# trapezoid.net
KiCad netlist of a schematic drawn in EAGLE
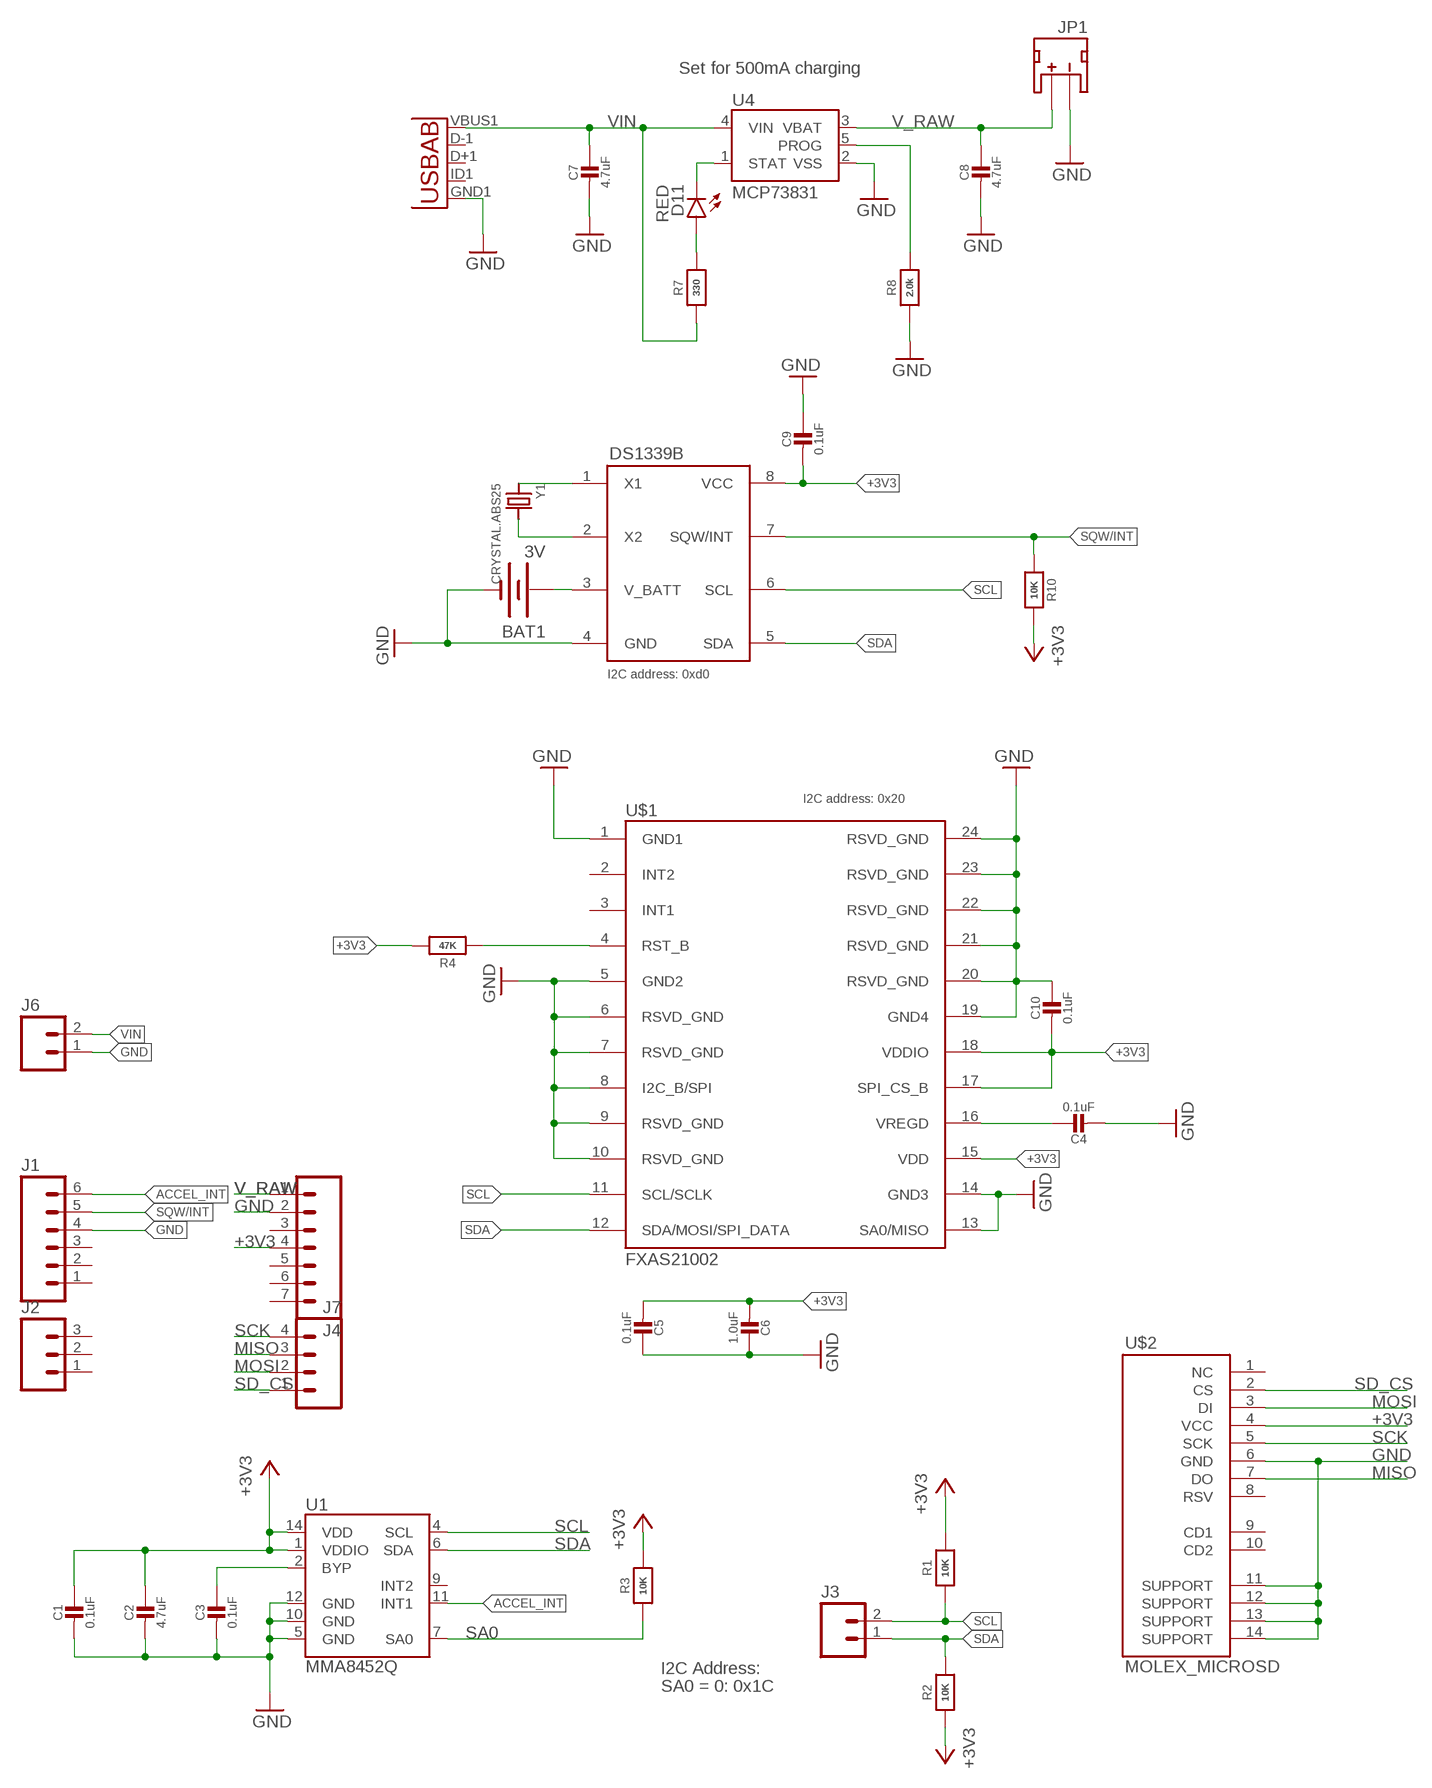
[diagram p0: schematic, sheet 1]

(export (version "E")
  (design (tool "Eeschema 10.0.6"))
  (components
    (comp (ref "BAT1")
      (value "3V")
      (footprint "eagle-import:BATTCON_12MM_CURVED")
      (libsource (lib "eagle-import") (part "BATTERY"))
    )
    (comp (ref "C1")
      (value "0.1uF")
      (footprint "eagle-import:0805-NO")
      (libsource (lib "eagle-import") (part "CAP_CERAMIC0805-NOOUTLINE"))
    )
    (comp (ref "C2")
      (value "4.7uF")
      (footprint "eagle-import:0805-NO")
      (libsource (lib "eagle-import") (part "CAP_CERAMIC0805-NOOUTLINE"))
    )
    (comp (ref "C3")
      (value "0.1uF")
      (footprint "eagle-import:0805-NO")
      (libsource (lib "eagle-import") (part "CAP_CERAMIC0805-NOOUTLINE"))
    )
    (comp (ref "C4")
      (value "0.1uF")
      (footprint "eagle-import:0805-NO")
      (libsource (lib "eagle-import") (part "CAP_CERAMIC0805-NOOUTLINE"))
    )
    (comp (ref "C5")
      (value "0.1uF")
      (footprint "eagle-import:0805-NO")
      (libsource (lib "eagle-import") (part "CAP_CERAMIC0805-NOOUTLINE"))
    )
    (comp (ref "C6")
      (value "1.0uF")
      (footprint "eagle-import:0805-NO")
      (libsource (lib "eagle-import") (part "CAP_CERAMIC0805-NOOUTLINE"))
    )
    (comp (ref "C7")
      (value "4.7uF")
      (footprint "eagle-import:0805-NO")
      (libsource (lib "eagle-import") (part "CAP_CERAMIC0805-NOOUTLINE"))
    )
    (comp (ref "C8")
      (value "4.7uF")
      (footprint "eagle-import:0805-NO")
      (libsource (lib "eagle-import") (part "CAP_CERAMIC0805-NOOUTLINE"))
    )
    (comp (ref "C9")
      (value "0.1uF")
      (footprint "eagle-import:0805-NO")
      (libsource (lib "eagle-import") (part "CAP_CERAMIC0805-NOOUTLINE"))
    )
    (comp (ref "C10")
      (value "0.1uF")
      (footprint "eagle-import:0805-NO")
      (libsource (lib "eagle-import") (part "CAP_CERAMIC0805-NOOUTLINE"))
    )
    (comp (ref "D11")
      (value "RED")
      (footprint "eagle-import:LED-0603")
      (libsource (lib "eagle-import") (part "LED-RED0603"))
    )
    (comp (ref "J1")
      (value "M06SILK_FEMALE_PTH")
      (footprint "eagle-import:1X06")
      (libsource (lib "eagle-import") (part "M06SILK_FEMALE_PTH"))
    )
    (comp (ref "J2")
      (value "M03PTH")
      (footprint "eagle-import:1X03")
      (libsource (lib "eagle-import") (part "M03PTH"))
    )
    (comp (ref "J3")
      (value "M02LOCK")
      (footprint "eagle-import:1X02_LOCK")
      (libsource (lib "eagle-import") (part "M02LOCK"))
    )
    (comp (ref "J4")
      (value "M07")
      (footprint "eagle-import:1X07")
      (libsource (lib "eagle-import") (part "M07"))
    )
    (comp (ref "J6")
      (value "M02LOCK")
      (footprint "eagle-import:1X02_LOCK")
      (libsource (lib "eagle-import") (part "M02LOCK"))
    )
    (comp (ref "J7")
      (value "M04PTH")
      (footprint "eagle-import:1X04")
      (libsource (lib "eagle-import") (part "M04PTH"))
    )
    (comp (ref "JP1")
      (value "JST")
      (footprint "eagle-import:JST-2-SMD@1")
      (libsource (lib "eagle-import") (part "JST_2MM_MALE"))
    )
    (comp (ref "JP9")
      (value "Micro USB")
      (footprint "eagle-import:USB-AB-MICRO-SMD_V03")
      (libsource (lib "eagle-import") (part "USB-ABCONN-11794"))
    )
    (comp (ref "R1")
      (value "10K")
      (footprint "eagle-import:0805-NO")
      (libsource (lib "eagle-import") (part "RESISTOR0805_NOOUTLINE"))
    )
    (comp (ref "R2")
      (value "10K")
      (footprint "eagle-import:0805-NO")
      (libsource (lib "eagle-import") (part "RESISTOR0805_NOOUTLINE"))
    )
    (comp (ref "R3")
      (value "10K")
      (footprint "eagle-import:_0805MP")
      (libsource (lib "eagle-import") (part "RESISTOR_0805MP"))
    )
    (comp (ref "R4")
      (value "47K")
      (footprint "eagle-import:0805-NO")
      (libsource (lib "eagle-import") (part "RESISTOR0805_NOOUTLINE"))
    )
    (comp (ref "R7")
      (value "330")
      (footprint "eagle-import:_0805MP")
      (libsource (lib "eagle-import") (part "RESISTOR_0805MP"))
    )
    (comp (ref "R8")
      (value "2.0k")
      (footprint "eagle-import:_0805MP")
      (libsource (lib "eagle-import") (part "RESISTOR_0805MP"))
    )
    (comp (ref "R10")
      (value "10K")
      (footprint "eagle-import:0805-NO")
      (libsource (lib "eagle-import") (part "RESISTOR0805_NOOUTLINE"))
    )
    (comp (ref "U$1")
      (value "FXAS21002")
      (footprint "eagle-import:24QFN")
      (libsource (lib "eagle-import") (part "FXAS21002"))
    )
    (comp (ref "U$2")
      (value "MOLEX_MICROSD")
      (footprint "eagle-import:MOLEX_MICROSD")
      (libsource (lib "eagle-import") (part "MOLEX_MICROSD"))
    )
    (comp (ref "U$3")
      (value "DS1339BDS1339B")
      (footprint "eagle-import:8U-SOP")
      (libsource (lib "eagle-import") (part "DS1339BDS1339B"))
    )
    (comp (ref "U1")
      (value "MMA8452Q")
      (footprint "eagle-import:QFN-16_0.5MM")
      (libsource (lib "eagle-import") (part "MMA8452Q"))
    )
    (comp (ref "U4")
      (value "MCP73831")
      (footprint "eagle-import:SOT23-5")
      (libsource (lib "eagle-import") (part "MCP73831"))
    )
    (comp (ref "Y1")
      (value "CRYSTAL.ABS25")
      (footprint "eagle-import:ABS25")
      (libsource (lib "eagle-import") (part "CRYSTAL.ABS25"))
    )
  )
  (nets
    (net (code "1") (name "+3V3") (class "Default")
      (node (ref "C1") (pin "1") (pinfunction "1_1") (pintype "passive"))
      (node (ref "C10") (pin "2") (pinfunction "2_2") (pintype "passive"))
      (node (ref "C2") (pin "1") (pinfunction "1_1") (pintype "passive"))
      (node (ref "C5") (pin "2") (pinfunction "2_2") (pintype "passive"))
      (node (ref "C6") (pin "2") (pinfunction "2_2") (pintype "passive"))
      (node (ref "C9") (pin "2") (pinfunction "2_2") (pintype "passive"))
      (node (ref "J4") (pin "4") (pinfunction "4_4") (pintype "passive"))
      (node (ref "R1") (pin "2") (pinfunction "2_2") (pintype "passive"))
      (node (ref "R10") (pin "2") (pinfunction "2_2") (pintype "passive"))
      (node (ref "R2") (pin "1") (pinfunction "1_1") (pintype "passive"))
      (node (ref "R3") (pin "2") (pinfunction "2_2") (pintype "passive"))
      (node (ref "R4") (pin "2") (pinfunction "2_2") (pintype "passive"))
      (node (ref "U$1") (pin "15") (pinfunction "VDD_15") (pintype "bidirectional"))
      (node (ref "U$1") (pin "17") (pinfunction "SPI_CS_B_17") (pintype "bidirectional"))
      (node (ref "U$1") (pin "18") (pinfunction "VDDIO_18") (pintype "bidirectional"))
      (node (ref "U$2") (pin "4") (pinfunction "VCC_4") (pintype "power_in"))
      (node (ref "U$3") (pin "8") (pinfunction "VCC_8") (pintype "bidirectional"))
      (node (ref "U1") (pin "1") (pinfunction "VDDIO_1") (pintype "bidirectional"))
      (node (ref "U1") (pin "14") (pinfunction "VDD_14") (pintype "bidirectional"))
    )
    (net (code "2") (name "/MISO") (class "Default")
      (node (ref "J7") (pin "3") (pinfunction "3_3") (pintype "passive"))
      (node (ref "U$2") (pin "7") (pinfunction "DO_7") (pintype "output"))
    )
    (net (code "3") (name "/MOSI") (class "Default")
      (node (ref "J7") (pin "2") (pinfunction "2_2") (pintype "passive"))
      (node (ref "U$2") (pin "3") (pinfunction "DI_3") (pintype "input"))
    )
    (net (code "4") (name "/SA0") (class "Default")
      (node (ref "R3") (pin "1") (pinfunction "1_1") (pintype "passive"))
      (node (ref "U1") (pin "7") (pinfunction "SA0_7") (pintype "bidirectional"))
    )
    (net (code "5") (name "/SCK") (class "Default")
      (node (ref "J7") (pin "4") (pinfunction "4_4") (pintype "passive"))
      (node (ref "U$2") (pin "5") (pinfunction "SCK_5") (pintype "bidirectional"))
    )
    (net (code "6") (name "/SD_CS") (class "Default")
      (node (ref "J7") (pin "1") (pinfunction "1_1") (pintype "passive"))
      (node (ref "U$2") (pin "2") (pinfunction "CS_2") (pintype "input"))
    )
    (net (code "7") (name "/V_RAW") (class "Default")
      (node (ref "C8") (pin "1") (pinfunction "1_1") (pintype "passive"))
      (node (ref "J4") (pin "1") (pinfunction "1_1") (pintype "passive"))
      (node (ref "JP1") (pin "2") (pinfunction "+_2") (pintype "bidirectional"))
      (node (ref "U4") (pin "3") (pinfunction "VBAT_3") (pintype "power_in"))
    )
    (net (code "8") (name "ACCEL_INT") (class "Default")
      (node (ref "J1") (pin "6") (pinfunction "6_6") (pintype "passive"))
      (node (ref "U1") (pin "11") (pinfunction "INT1_11") (pintype "bidirectional"))
    )
    (net (code "9") (name "GND") (class "Default")
      (node (ref "BAT1") (pin "GND") (pinfunction "-_GND") (pintype "power_in"))
      (node (ref "C1") (pin "2") (pinfunction "2_2") (pintype "passive"))
      (node (ref "C10") (pin "1") (pinfunction "1_1") (pintype "passive"))
      (node (ref "C2") (pin "2") (pinfunction "2_2") (pintype "passive"))
      (node (ref "C3") (pin "2") (pinfunction "2_2") (pintype "passive"))
      (node (ref "C4") (pin "2") (pinfunction "2_2") (pintype "passive"))
      (node (ref "C5") (pin "1") (pinfunction "1_1") (pintype "passive"))
      (node (ref "C6") (pin "1") (pinfunction "1_1") (pintype "passive"))
      (node (ref "C7") (pin "2") (pinfunction "2_2") (pintype "passive"))
      (node (ref "C8") (pin "2") (pinfunction "2_2") (pintype "passive"))
      (node (ref "C9") (pin "1") (pinfunction "1_1") (pintype "passive"))
      (node (ref "J1") (pin "4") (pinfunction "4_4") (pintype "passive"))
      (node (ref "J4") (pin "2") (pinfunction "2_2") (pintype "passive"))
      (node (ref "J6") (pin "1") (pinfunction "1_1") (pintype "passive"))
      (node (ref "JP1") (pin "1") (pinfunction "-_1") (pintype "bidirectional"))
      (node (ref "JP9") (pin "GND1") (pinfunction "GND_GND1") (pintype "bidirectional"))
      (node (ref "R8") (pin "1") (pinfunction "1_1") (pintype "passive"))
      (node (ref "U$1") (pin "1") (pinfunction "GND1_1") (pintype "bidirectional"))
      (node (ref "U$1") (pin "10") (pinfunction "RSVD_GND_10") (pintype "bidirectional"))
      (node (ref "U$1") (pin "13") (pinfunction "SA0/MISO_13") (pintype "bidirectional"))
      (node (ref "U$1") (pin "14") (pinfunction "GND3_14") (pintype "bidirectional"))
      (node (ref "U$1") (pin "19") (pinfunction "GND4_19") (pintype "bidirectional"))
      (node (ref "U$1") (pin "20") (pinfunction "RSVD_GND_20") (pintype "bidirectional"))
      (node (ref "U$1") (pin "21") (pinfunction "RSVD_GND_21") (pintype "bidirectional"))
      (node (ref "U$1") (pin "22") (pinfunction "RSVD_GND_22") (pintype "bidirectional"))
      (node (ref "U$1") (pin "23") (pinfunction "RSVD_GND_23") (pintype "bidirectional"))
      (node (ref "U$1") (pin "24") (pinfunction "RSVD_GND_24") (pintype "bidirectional"))
      (node (ref "U$1") (pin "5") (pinfunction "GND2_5") (pintype "bidirectional"))
      (node (ref "U$1") (pin "6") (pinfunction "RSVD_GND_6") (pintype "bidirectional"))
      (node (ref "U$1") (pin "7") (pinfunction "RSVD_GND_7") (pintype "bidirectional"))
      (node (ref "U$1") (pin "8") (pinfunction "I2C_B/SPI_8") (pintype "bidirectional"))
      (node (ref "U$1") (pin "9") (pinfunction "RSVD_GND_9") (pintype "bidirectional"))
      (node (ref "U$2") (pin "11") (pinfunction "SUPPORT_11") (pintype "power_in"))
      (node (ref "U$2") (pin "12") (pinfunction "SUPPORT_12") (pintype "power_in"))
      (node (ref "U$2") (pin "13") (pinfunction "SUPPORT_13") (pintype "power_in"))
      (node (ref "U$2") (pin "14") (pinfunction "SUPPORT_14") (pintype "power_in"))
      (node (ref "U$2") (pin "6") (pinfunction "GND_6") (pintype "power_in"))
      (node (ref "U$3") (pin "4") (pinfunction "GND_4") (pintype "bidirectional"))
      (node (ref "U1") (pin "10") (pinfunction "GND_10") (pintype "bidirectional"))
      (node (ref "U1") (pin "12") (pinfunction "GND_12") (pintype "bidirectional"))
      (node (ref "U1") (pin "5") (pinfunction "GND_5") (pintype "bidirectional"))
      (node (ref "U4") (pin "2") (pinfunction "VSS_2") (pintype "power_in"))
    )
    (net (code "10") (name "Net-(BAT1-+)") (class "Default")
      (node (ref "BAT1") (pin "PWR@1") (pinfunction "+_PWR@1") (pintype "power_in"))
      (node (ref "U$3") (pin "3") (pinfunction "V_BATT_3") (pintype "bidirectional"))
    )
    (net (code "11") (name "Net-(D11-PadA)") (class "Default")
      (node (ref "D11") (pin "A") (pinfunction "A_A") (pintype "passive"))
      (node (ref "R7") (pin "2") (pinfunction "2_2") (pintype "passive"))
    )
    (net (code "12") (name "Net-(U$1-RST_B)") (class "Default")
      (node (ref "R4") (pin "1") (pinfunction "1_1") (pintype "passive"))
      (node (ref "U$1") (pin "4") (pinfunction "RST_B_4") (pintype "bidirectional"))
    )
    (net (code "13") (name "Net-(U$1-VREGD)") (class "Default")
      (node (ref "C4") (pin "1") (pinfunction "1_1") (pintype "passive"))
      (node (ref "U$1") (pin "16") (pinfunction "VREGD_16") (pintype "bidirectional"))
    )
    (net (code "14") (name "Net-(U$3-X1)") (class "Default")
      (node (ref "U$3") (pin "1") (pinfunction "X1_1") (pintype "bidirectional"))
      (node (ref "Y1") (pin "1") (pinfunction "1_1") (pintype "passive"))
    )
    (net (code "15") (name "Net-(U$3-X2)") (class "Default")
      (node (ref "U$3") (pin "2") (pinfunction "X2_2") (pintype "bidirectional"))
      (node (ref "Y1") (pin "4") (pinfunction "2_4") (pintype "passive"))
    )
    (net (code "16") (name "Net-(U1-BYP)") (class "Default")
      (node (ref "C3") (pin "1") (pinfunction "1_1") (pintype "passive"))
      (node (ref "U1") (pin "2") (pinfunction "BYP_2") (pintype "bidirectional"))
    )
    (net (code "17") (name "Net-(U4-PROG)") (class "Default")
      (node (ref "R8") (pin "2") (pinfunction "2_2") (pintype "passive"))
      (node (ref "U4") (pin "5") (pinfunction "PROG_5") (pintype "input"))
    )
    (net (code "18") (name "Net-(U4-STAT)") (class "Default")
      (node (ref "D11") (pin "C") (pinfunction "C_C") (pintype "passive"))
      (node (ref "U4") (pin "1") (pinfunction "STAT_1") (pintype "output"))
    )
    (net (code "19") (name "SCL") (class "Default")
      (node (ref "J3") (pin "2") (pinfunction "2_2") (pintype "passive"))
      (node (ref "R1") (pin "1") (pinfunction "1_1") (pintype "passive"))
      (node (ref "U$1") (pin "11") (pinfunction "SCL/SCLK_11") (pintype "bidirectional"))
      (node (ref "U$3") (pin "6") (pinfunction "SCL_6") (pintype "bidirectional"))
      (node (ref "U1") (pin "4") (pinfunction "SCL_4") (pintype "bidirectional"))
    )
    (net (code "20") (name "SDA") (class "Default")
      (node (ref "J3") (pin "1") (pinfunction "1_1") (pintype "passive"))
      (node (ref "R2") (pin "2") (pinfunction "2_2") (pintype "passive"))
      (node (ref "U$1") (pin "12") (pinfunction "SDA/MOSI/SPI_DATA_12") (pintype "bidirectional"))
      (node (ref "U$3") (pin "5") (pinfunction "SDA_5") (pintype "bidirectional"))
      (node (ref "U1") (pin "6") (pinfunction "SDA_6") (pintype "bidirectional"))
    )
    (net (code "21") (name "SQW{slash}INT") (class "Default")
      (node (ref "J1") (pin "5") (pinfunction "5_5") (pintype "passive"))
      (node (ref "R10") (pin "1") (pinfunction "1_1") (pintype "passive"))
      (node (ref "U$3") (pin "7") (pinfunction "SQW/INT_7") (pintype "bidirectional"))
    )
    (net (code "22") (name "VIN") (class "Default")
      (node (ref "C7") (pin "1") (pinfunction "1_1") (pintype "passive"))
      (node (ref "J6") (pin "2") (pinfunction "2_2") (pintype "passive"))
      (node (ref "JP9") (pin "VBUS1") (pinfunction "VBUS_VBUS1") (pintype "bidirectional"))
      (node (ref "R7") (pin "1") (pinfunction "1_1") (pintype "passive"))
      (node (ref "U4") (pin "4") (pinfunction "VIN_4") (pintype "power_in"))
    )
    (net (code "23") (name "unconnected-(J1-Pad1)") (class "Default")
      (node (ref "J1") (pin "1") (pinfunction "1_1") (pintype "passive"))
    )
    (net (code "24") (name "unconnected-(J1-Pad2)") (class "Default")
      (node (ref "J1") (pin "2") (pinfunction "2_2") (pintype "passive"))
    )
    (net (code "25") (name "unconnected-(J1-Pad3)") (class "Default")
      (node (ref "J1") (pin "3") (pinfunction "3_3") (pintype "passive"))
    )
    (net (code "26") (name "unconnected-(J2-Pad1)") (class "Default")
      (node (ref "J2") (pin "1") (pinfunction "1_1") (pintype "passive"))
    )
    (net (code "27") (name "unconnected-(J2-Pad2)") (class "Default")
      (node (ref "J2") (pin "2") (pinfunction "2_2") (pintype "passive"))
    )
    (net (code "28") (name "unconnected-(J2-Pad3)") (class "Default")
      (node (ref "J2") (pin "3") (pinfunction "3_3") (pintype "passive"))
    )
    (net (code "29") (name "unconnected-(J4-Pad3)") (class "Default")
      (node (ref "J4") (pin "3") (pinfunction "3_3") (pintype "passive"))
    )
    (net (code "30") (name "unconnected-(J4-Pad5)") (class "Default")
      (node (ref "J4") (pin "5") (pinfunction "5_5") (pintype "passive"))
    )
    (net (code "31") (name "unconnected-(J4-Pad6)") (class "Default")
      (node (ref "J4") (pin "6") (pinfunction "6_6") (pintype "passive"))
    )
    (net (code "32") (name "unconnected-(J4-Pad7)") (class "Default")
      (node (ref "J4") (pin "7") (pinfunction "7_7") (pintype "passive"))
    )
    (net (code "33") (name "unconnected-(JP1-PAD1-PadNC1)") (class "Default")
      (node (ref "JP1") (pin "NC1") (pinfunction "PAD1_NC1") (pintype "bidirectional"))
    )
    (net (code "34") (name "unconnected-(JP1-PAD2-PadNC2)") (class "Default")
      (node (ref "JP1") (pin "NC2") (pinfunction "PAD2_NC2") (pintype "bidirectional"))
    )
    (net (code "35") (name "unconnected-(JP9-D+-PadD+1)") (class "Default")
      (node (ref "JP9") (pin "D+1") (pinfunction "D+_D+1") (pintype "bidirectional"))
    )
    (net (code "36") (name "unconnected-(JP9-D--PadD-1)") (class "Default")
      (node (ref "JP9") (pin "D-1") (pinfunction "D-_D-1") (pintype "bidirectional"))
    )
    (net (code "37") (name "unconnected-(JP9-USBID-PadID1)") (class "Default")
      (node (ref "JP9") (pin "ID1") (pinfunction "USBID_ID1") (pintype "bidirectional"))
    )
    (net (code "38") (name "unconnected-(U$1-INT1-Pad3)") (class "Default")
      (node (ref "U$1") (pin "3") (pinfunction "INT1_3") (pintype "bidirectional"))
    )
    (net (code "39") (name "unconnected-(U$1-INT2-Pad2)") (class "Default")
      (node (ref "U$1") (pin "2") (pinfunction "INT2_2") (pintype "bidirectional"))
    )
    (net (code "40") (name "unconnected-(U$2-CD1-Pad9)") (class "Default")
      (node (ref "U$2") (pin "9") (pinfunction "CD1_9") (pintype "bidirectional"))
    )
    (net (code "41") (name "unconnected-(U$2-CD2-Pad10)") (class "Default")
      (node (ref "U$2") (pin "10") (pinfunction "CD2_10") (pintype "bidirectional"))
    )
    (net (code "42") (name "unconnected-(U$2-NC-Pad1)") (class "Default")
      (node (ref "U$2") (pin "1") (pinfunction "NC_1") (pintype "no_connect"))
    )
    (net (code "43") (name "unconnected-(U$2-RSV-Pad8)") (class "Default")
      (node (ref "U$2") (pin "8") (pinfunction "RSV_8") (pintype "bidirectional"))
    )
    (net (code "44") (name "unconnected-(U1-INT2-Pad9)") (class "Default")
      (node (ref "U1") (pin "9") (pinfunction "INT2_9") (pintype "bidirectional"))
    )
  )
)
